# FilterSupply.net
KiCad netlist of a schematic drawn in EAGLE
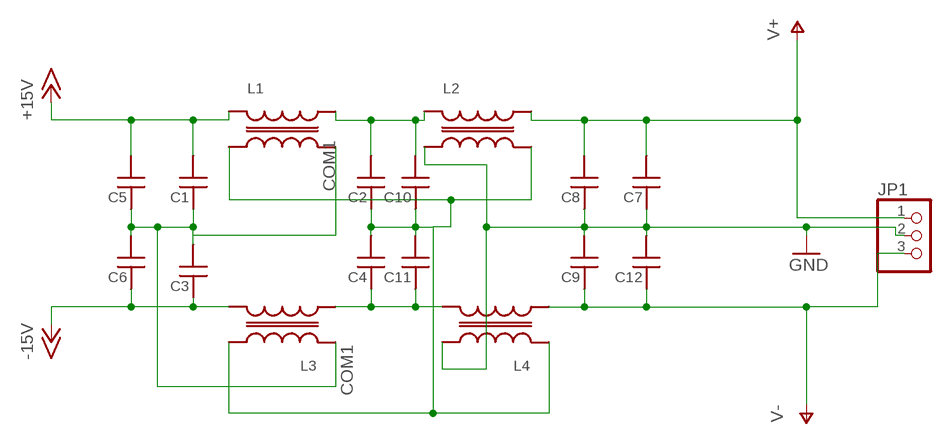
[diagram p0: schematic, sheet 1]

(export (version "E")
  (design (tool "Eeschema 10.0.6"))
  (components
    (comp (ref "C1")
      (value "C_MLCC_SMDCMLCC_0805")
      (footprint "eagle-import:C_MLCC_0805")
      (libsource (lib "eagle-import") (part "C_MLCC_SMDCMLCC_0805"))
    )
    (comp (ref "C2")
      (value "C_MLCC_SMDCMLCC_0603")
      (footprint "eagle-import:C_MLCC_0603")
      (libsource (lib "eagle-import") (part "C_MLCC_SMDCMLCC_0603"))
    )
    (comp (ref "C3")
      (value "C_MLCC_SMDCMLCC_0805")
      (footprint "eagle-import:C_MLCC_0805")
      (libsource (lib "eagle-import") (part "C_MLCC_SMDCMLCC_0805"))
    )
    (comp (ref "C4")
      (value "C_MLCC_SMDCMLCC_0603")
      (footprint "eagle-import:C_MLCC_0603")
      (libsource (lib "eagle-import") (part "C_MLCC_SMDCMLCC_0603"))
    )
    (comp (ref "C5")
      (value "C_MLCC_SMDCMLCC_0805")
      (footprint "eagle-import:C_MLCC_0805")
      (libsource (lib "eagle-import") (part "C_MLCC_SMDCMLCC_0805"))
    )
    (comp (ref "C6")
      (value "C_MLCC_SMDCMLCC_0805")
      (footprint "eagle-import:C_MLCC_0805")
      (libsource (lib "eagle-import") (part "C_MLCC_SMDCMLCC_0805"))
    )
    (comp (ref "C7")
      (value "C_MLCC_SMDCMLCC_0603")
      (footprint "eagle-import:C_MLCC_0603")
      (libsource (lib "eagle-import") (part "C_MLCC_SMDCMLCC_0603"))
    )
    (comp (ref "C8")
      (value "C_MLCC_SMDCMLCC_0603")
      (footprint "eagle-import:C_MLCC_0603")
      (libsource (lib "eagle-import") (part "C_MLCC_SMDCMLCC_0603"))
    )
    (comp (ref "C9")
      (value "C_MLCC_SMDCMLCC_0603")
      (footprint "eagle-import:C_MLCC_0603")
      (libsource (lib "eagle-import") (part "C_MLCC_SMDCMLCC_0603"))
    )
    (comp (ref "C10")
      (value "C_MLCC_SMDCMLCC_0603")
      (footprint "eagle-import:C_MLCC_0603")
      (libsource (lib "eagle-import") (part "C_MLCC_SMDCMLCC_0603"))
    )
    (comp (ref "C11")
      (value "C_MLCC_SMDCMLCC_0603")
      (footprint "eagle-import:C_MLCC_0603")
      (libsource (lib "eagle-import") (part "C_MLCC_SMDCMLCC_0603"))
    )
    (comp (ref "C12")
      (value "C_MLCC_SMDCMLCC_0603")
      (footprint "eagle-import:C_MLCC_0603")
      (libsource (lib "eagle-import") (part "C_MLCC_SMDCMLCC_0603"))
    )
    (comp (ref "JP1")
      (value "PINHD-1X3")
      (footprint "eagle-import:1X03")
      (libsource (lib "eagle-import") (part "PINHD-1X3"))
    )
    (comp (ref "L1")
      (value "MSD7342")
      (footprint "eagle-import:MSD7342")
      (libsource (lib "eagle-import") (part "MSD7342"))
    )
    (comp (ref "L2")
      (value "MSD7342")
      (footprint "eagle-import:MSD7342")
      (libsource (lib "eagle-import") (part "MSD7342"))
    )
    (comp (ref "L3")
      (value "MSD7342")
      (footprint "eagle-import:MSD7342")
      (libsource (lib "eagle-import") (part "MSD7342"))
    )
    (comp (ref "L4")
      (value "MSD7342")
      (footprint "eagle-import:MSD7342")
      (libsource (lib "eagle-import") (part "MSD7342"))
    )
  )
  (nets
    (net (code "1") (name "+15V") (class "Default")
      (node (ref "C1") (pin "P$2") (pinfunction "2_P$2") (pintype "passive"))
      (node (ref "C5") (pin "P$2") (pinfunction "2_P$2") (pintype "passive"))
      (node (ref "L1") (pin "2") (pinfunction "2_2") (pintype "passive"))
    )
    (net (code "2") (name "-15V") (class "Default")
      (node (ref "C3") (pin "P$1") (pinfunction "1_P$1") (pintype "passive"))
      (node (ref "C6") (pin "P$1") (pinfunction "1_P$1") (pintype "passive"))
      (node (ref "L3") (pin "3") (pinfunction "3_3") (pintype "passive"))
    )
    (net (code "3") (name "/COM1") (class "Default")
      (node (ref "C1") (pin "P$1") (pinfunction "1_P$1") (pintype "passive"))
      (node (ref "C3") (pin "P$2") (pinfunction "2_P$2") (pintype "passive"))
      (node (ref "C5") (pin "P$1") (pinfunction "1_P$1") (pintype "passive"))
      (node (ref "C6") (pin "P$2") (pinfunction "2_P$2") (pintype "passive"))
      (node (ref "L1") (pin "3") (pinfunction "3_3") (pintype "passive"))
      (node (ref "L3") (pin "2") (pinfunction "2_2") (pintype "passive"))
    )
    (net (code "4") (name "GND") (class "Default")
      (node (ref "C12") (pin "P$2") (pinfunction "2_P$2") (pintype "passive"))
      (node (ref "C7") (pin "P$1") (pinfunction "1_P$1") (pintype "passive"))
      (node (ref "C8") (pin "P$1") (pinfunction "1_P$1") (pintype "passive"))
      (node (ref "C9") (pin "P$2") (pinfunction "2_P$2") (pintype "passive"))
      (node (ref "JP1") (pin "2") (pinfunction "2_2") (pintype "passive"))
      (node (ref "L2") (pin "1") (pinfunction "1_1") (pintype "passive"))
      (node (ref "L4") (pin "4") (pinfunction "4_4") (pintype "passive"))
    )
    (net (code "5") (name "Net-(C10-1)") (class "Default")
      (node (ref "C10") (pin "P$1") (pinfunction "1_P$1") (pintype "passive"))
      (node (ref "C11") (pin "P$2") (pinfunction "2_P$2") (pintype "passive"))
      (node (ref "C2") (pin "P$1") (pinfunction "1_P$1") (pintype "passive"))
      (node (ref "C4") (pin "P$2") (pinfunction "2_P$2") (pintype "passive"))
      (node (ref "L1") (pin "1") (pinfunction "1_1") (pintype "passive"))
      (node (ref "L2") (pin "3") (pinfunction "3_3") (pintype "passive"))
      (node (ref "L3") (pin "4") (pinfunction "4_4") (pintype "passive"))
      (node (ref "L4") (pin "2") (pinfunction "2_2") (pintype "passive"))
    )
    (net (code "6") (name "Net-(C10-2)") (class "Default")
      (node (ref "C10") (pin "P$2") (pinfunction "2_P$2") (pintype "passive"))
      (node (ref "C2") (pin "P$2") (pinfunction "2_P$2") (pintype "passive"))
      (node (ref "L1") (pin "4") (pinfunction "4_4") (pintype "passive"))
      (node (ref "L2") (pin "2") (pinfunction "2_2") (pintype "passive"))
    )
    (net (code "7") (name "Net-(C11-1)") (class "Default")
      (node (ref "C11") (pin "P$1") (pinfunction "1_P$1") (pintype "passive"))
      (node (ref "C4") (pin "P$1") (pinfunction "1_P$1") (pintype "passive"))
      (node (ref "L3") (pin "1") (pinfunction "1_1") (pintype "passive"))
      (node (ref "L4") (pin "3") (pinfunction "3_3") (pintype "passive"))
    )
    (net (code "8") (name "V+") (class "Default")
      (node (ref "C7") (pin "P$2") (pinfunction "2_P$2") (pintype "passive"))
      (node (ref "C8") (pin "P$2") (pinfunction "2_P$2") (pintype "passive"))
      (node (ref "JP1") (pin "1") (pinfunction "1_1") (pintype "passive"))
      (node (ref "L2") (pin "4") (pinfunction "4_4") (pintype "passive"))
    )
    (net (code "9") (name "V-") (class "Default")
      (node (ref "C12") (pin "P$1") (pinfunction "1_P$1") (pintype "passive"))
      (node (ref "C9") (pin "P$1") (pinfunction "1_P$1") (pintype "passive"))
      (node (ref "JP1") (pin "3") (pinfunction "3_3") (pintype "passive"))
      (node (ref "L4") (pin "1") (pinfunction "1_1") (pintype "passive"))
    )
  )
)
